# Motor-E.net
KiCad netlist of a schematic drawn in Altium Designer
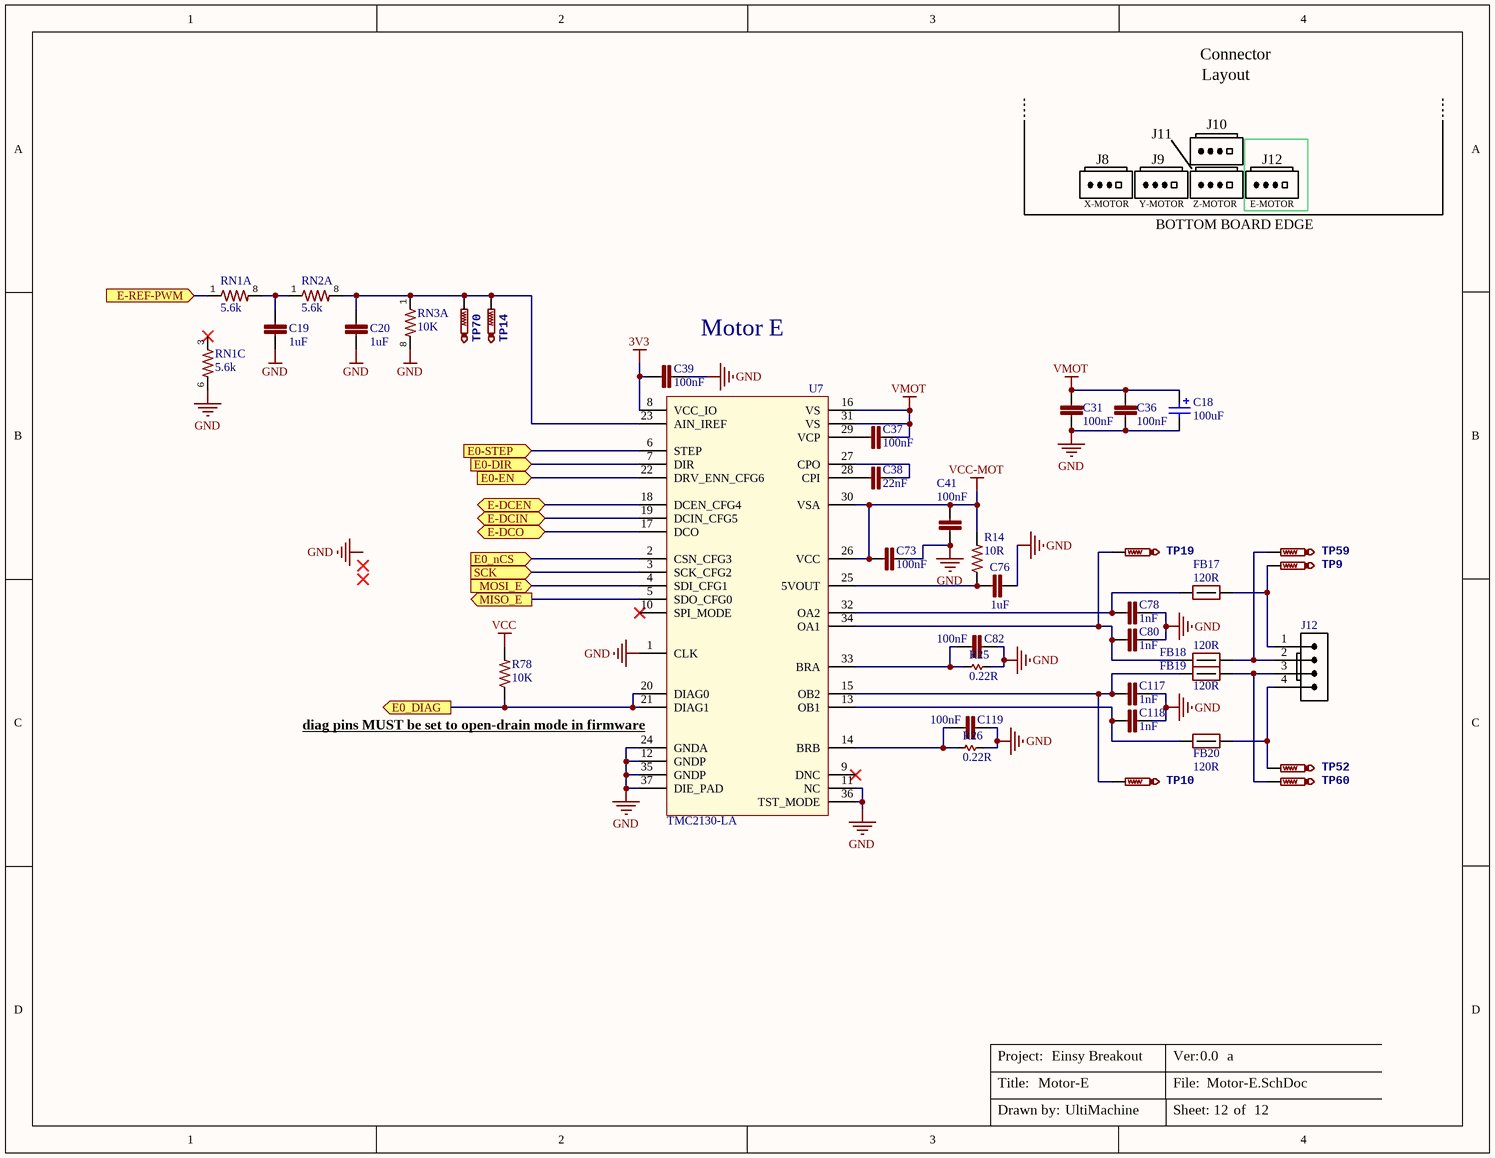
[diagram p0: Motor-E.SchDoc]

(export (version "E")
  (design (tool "Eeschema 10.0.6"))
  (components
    (comp (ref "C18")
      (value "100uF")
      (footprint "CAP-ELEC-063063077")
      (description "CAP ALUM 100UF 35V 20% SMD")
      (fields (field (name "MANUFACTURER") "Nichicon") (field (name "TOLERANCE") "+/- 20%"))
      (libsource (lib "3Delight") (part "UWT1V101MCL1GS"))
    )
    (comp (ref "C19")
      (value "1uF")
      (footprint "C0402")
      (description "CAP CER 0402 1uF 6.3V 10% X5R")
      (fields (field (name "MANUFACTURER") "Murata") (field (name "TOLERANCE") "+/- 10%"))
      (libsource (lib "3Delight") (part "GRM155R60J105KE19D"))
    )
    (comp (ref "C20")
      (value "1uF")
      (footprint "C0402")
      (description "CAP CER 0402 1uF 6.3V 10% X5R")
      (fields (field (name "MANUFACTURER") "Murata") (field (name "TOLERANCE") "+/- 10%"))
      (libsource (lib "3Delight") (part "GRM155R60J105KE19D"))
    )
    (comp (ref "C31")
      (value "100nF")
      (footprint "C0603")
      (description "CAP CER 0603 100nF 50V 10% X7R")
      (fields (field (name "MANUFACTURER") "Kemet") (field (name "TOLERANCE") "+/- 10%"))
      (libsource (lib "") (part "C0603C104K5RACTU_1"))
    )
    (comp (ref "C36")
      (value "100nF")
      (footprint "C0603")
      (description "CAP CER 0603 100nF 50V 10% X7R")
      (fields (field (name "MANUFACTURER") "Kemet") (field (name "TOLERANCE") "+/- 10%"))
      (libsource (lib "") (part "C0603C104K5RACTU_1"))
    )
    (comp (ref "C37")
      (value "100nF")
      (footprint "C0603")
      (description "CAP CER 0603 100nF 50V 10% X7R")
      (fields (field (name "MANUFACTURER") "Kemet") (field (name "TOLERANCE") "+/- 10%"))
      (libsource (lib "") (part "C0603C104K5RACTU_2"))
    )
    (comp (ref "C38")
      (value "22nF")
      (footprint "C0402")
      (description "CAP CER 0402 22nF ±10% 50V X7R")
      (fields (field (name "MANUFACTURER") "YAGEO") (field (name "TOLERANCE") "+/- 10%"))
      (libsource (lib "3Delight") (part "GCM155R71H223KA55D"))
    )
    (comp (ref "C39")
      (value "100nF")
      (footprint "C0402")
      (description "CAP CER 0402 100nF 16V 10% X7R")
      (fields (field (name "MANUFACTURER") "Murata") (field (name "TOLERANCE") "+/- 10%"))
      (libsource (lib "") (part "GRM155R71C104KA88D_1"))
    )
    (comp (ref "C41")
      (value "100nF")
      (footprint "C0402")
      (description "CAP CER 0402 100nF 16V 10% X7R")
      (fields (field (name "MANUFACTURER") "Murata") (field (name "TOLERANCE") "+/- 10%"))
      (libsource (lib "3Delight") (part "GRM155R71C104KA88D"))
    )
    (comp (ref "C73")
      (value "100nF")
      (footprint "C0402")
      (description "CAP CER 0402 100nF 16V 10% X7R")
      (fields (field (name "MANUFACTURER") "Murata") (field (name "TOLERANCE") "+/- 10%"))
      (libsource (lib "") (part "GRM155R71C104KA88D_1"))
    )
    (comp (ref "C76")
      (value "1uF")
      (footprint "C0402")
      (description "CAP CER 0402 1uF 6.3V 10% X5R")
      (fields (field (name "MANUFACTURER") "Murata") (field (name "TOLERANCE") "+/- 10%"))
      (libsource (lib "") (part "GRM155R60J105KE19D_1"))
    )
    (comp (ref "C78")
      (value "1nF")
      (footprint "C0603")
      (description "CAP CER 0603  1nF 50v 10% X7R")
      (fields (field (name "MANUFACTURER") "Kemet") (field (name "TOLERANCE") "+/- 10%"))
      (libsource (lib "3Delight") (part "C0603C102K5RACTU"))
    )
    (comp (ref "C80")
      (value "1nF")
      (footprint "C0603")
      (description "CAP CER 0603  1nF 50v 10% X7R")
      (fields (field (name "MANUFACTURER") "Kemet") (field (name "TOLERANCE") "+/- 10%"))
      (libsource (lib "3Delight") (part "C0603C102K5RACTU"))
    )
    (comp (ref "C82")
      (value "100nF")
      (footprint "C0603")
      (description "CAP CER 0603 100nF 50V 10% X7R")
      (fields (field (name "MANUFACTURER") "Kemet") (field (name "TOLERANCE") "+/- 10%"))
      (libsource (lib "3Delight") (part "C0603C104K5RACTU"))
    )
    (comp (ref "C117")
      (value "1nF")
      (footprint "C0603")
      (description "CAP CER 0603  1nF 50v 10% X7R")
      (fields (field (name "MANUFACTURER") "Kemet") (field (name "TOLERANCE") "+/- 10%"))
      (libsource (lib "3Delight") (part "C0603C102K5RACTU"))
    )
    (comp (ref "C118")
      (value "1nF")
      (footprint "C0603")
      (description "CAP CER 0603  1nF 50v 10% X7R")
      (fields (field (name "MANUFACTURER") "Kemet") (field (name "TOLERANCE") "+/- 10%"))
      (libsource (lib "3Delight") (part "C0603C102K5RACTU"))
    )
    (comp (ref "C119")
      (value "100nF")
      (footprint "C0603")
      (description "CAP CER 0603 100nF 50V 10% X7R")
      (fields (field (name "MANUFACTURER") "Kemet") (field (name "TOLERANCE") "+/- 10%"))
      (libsource (lib "3Delight") (part "C0603C104K5RACTU"))
    )
    (comp (ref "FB17")
      (value "120R")
      (footprint "FB0603")
      (description "FERRITE BEAD 120 OHM 0603 1LN")
      (fields (field (name "MANUFACTURER") "Samsung") (field (name "PART") "FERRITE 120R 3A 0603"))
      (libsource (lib "Inductors") (part "FERRITE 120R 3A 0603"))
    )
    (comp (ref "FB18")
      (value "120R")
      (footprint "FB0603")
      (description "FERRITE BEAD 120 OHM 0603 1LN")
      (fields (field (name "MANUFACTURER") "Samsung") (field (name "PART") "FERRITE 120R 3A 0603"))
      (libsource (lib "Inductors") (part "FERRITE 120R 3A 0603"))
    )
    (comp (ref "FB19")
      (value "120R")
      (footprint "FB0603")
      (description "FERRITE BEAD 120 OHM 0603 1LN")
      (fields (field (name "MANUFACTURER") "Samsung") (field (name "PART") "FERRITE 120R 3A 0603"))
      (libsource (lib "Inductors") (part "FERRITE 120R 3A 0603"))
    )
    (comp (ref "FB20")
      (value "120R")
      (footprint "FB0603")
      (description "FERRITE BEAD 120 OHM 0603 1LN")
      (fields (field (name "MANUFACTURER") "Samsung") (field (name "PART") "FERRITE 120R 3A 0603"))
      (libsource (lib "Inductors") (part "FERRITE 120R 3A 0603"))
    )
    (comp (ref "J12")
      (value "Molex 0705430003")
      (footprint "4POL254")
      (description "Molex 4 Pin Clip Connector")
      (fields (field (name "MANUFACTURER") "Molex") (field (name "PART") "4 Pin Conn"))
      (libsource (lib "3Delight") (part "CONN 4PIN 0.1{dblquote} VERT SHRD LOCK ALT"))
    )
    (comp (ref "R14")
      (value "10R")
      (footprint "R0402")
      (description "RES SMD 10 OHM 1% 1/16W 0402")
      (fields (field (name "MANUFACTURER") "Yageo") (field (name "TOLERANCE") "+/- 1%"))
      (libsource (lib "3Delight") (part "RC0402FR-0710RL"))
    )
    (comp (ref "R25")
      (value "0.22R")
      (footprint "R1206")
      (description "RES SMD 0.22 OHM 1% 1/3W 1206")
      (fields (field (name "MANUFACTURER") "Panasonic") (field (name "TOLERANCE") "+/- 1%"))
      (libsource (lib "Resistors") (part "0.22R 1% 1206"))
    )
    (comp (ref "R26")
      (value "0.22R")
      (footprint "R1206")
      (description "RES SMD 0.22 OHM 1% 1/3W 1206")
      (fields (field (name "MANUFACTURER") "Panasonic") (field (name "TOLERANCE") "+/- 1%"))
      (libsource (lib "Resistors") (part "0.22R 1% 1206"))
    )
    (comp (ref "R78")
      (value "10K")
      (footprint "R0402")
      (description "RES SMD 10K OHM 1% 1/16W 0402")
      (fields (field (name "MANUFACTURER") "Yageo") (field (name "PART") "10k 1% 0402"))
      (libsource (lib "3Delight") (part "RC0402FR-0710KP"))
    )
    (comp (ref "RN1")
      (value "5.6k")
      (footprint "CAY16")
      (description "RES ARRAY 4 RES 5.6K OHM 1206")
      (fields (field (name "MANUFACTURER") "Bourns") (field (name "TOLERANCE") "+/- 5%"))
      (libsource (lib "Resistors") (part "5.6k x 4 5% 1206"))
    )
    (comp (ref "RN2")
      (value "5.6k")
      (footprint "CAY16")
      (description "RES ARRAY 4 RES 5.6K OHM 1206")
      (fields (field (name "MANUFACTURER") "Bourns") (field (name "TOLERANCE") "+/- 5%"))
      (libsource (lib "Resistors") (part "5.6k x 4 5% 1206"))
    )
    (comp (ref "RN3")
      (value "10K")
      (footprint "CAY16")
      (description "RES ARRAY 4 RES 10K 1206 62.5mW 5%")
      (fields (field (name "MANUFACTURER") "Bourns") (field (name "TOLERANCE") "+/- 5%"))
      (libsource (lib "3Delight") (part "CAY16-103J4LF"))
    )
    (comp (ref "TP9")
      (value "TestPoint")
      (footprint "TP1-27")
      (description "Test Point")
      (libsource (lib "3Delight") (part "TestPoint"))
    )
    (comp (ref "TP10")
      (value "TestPoint")
      (footprint "TP1-27")
      (description "Test Point")
      (libsource (lib "3Delight") (part "TestPoint"))
    )
    (comp (ref "TP14")
      (value "TestPoint")
      (footprint "TP1-27")
      (description "Test Point")
      (libsource (lib "") (part "TestPoint_1"))
    )
    (comp (ref "TP19")
      (value "TestPoint")
      (footprint "TP1-27")
      (description "Test Point")
      (libsource (lib "3Delight") (part "TestPoint"))
    )
    (comp (ref "TP52")
      (value "TestPoint")
      (footprint "TP1-27")
      (description "Test Point")
      (libsource (lib "3Delight") (part "TestPoint"))
    )
    (comp (ref "TP59")
      (value "TestPoint")
      (footprint "TP1-27")
      (description "Test Point")
      (libsource (lib "3Delight") (part "TestPoint"))
    )
    (comp (ref "TP60")
      (value "TestPoint")
      (footprint "TP1-27")
      (description "Test Point")
      (libsource (lib "3Delight") (part "TestPoint"))
    )
    (comp (ref "TP70")
      (value "TestPoint")
      (footprint "TP1-27")
      (description "Test Point")
      (libsource (lib "") (part "TestPoint_1"))
    )
    (comp (ref "U7")
      (value "TMC2130-LA")
      (footprint "QFN36-50P500X600X900_HS-37N")
      (description "IC STEPPER MOTOR DVR SPI 36QFN")
      (fields (field (name "MANUFACTURER") "Trinamic") (field (name "PART") "TMC2130"))
      (libsource (lib "ICs-Motor Controller") (part "TMC2130-LA-T"))
    )
  )
  (nets
    (net (code "1") (name "/E-DCEN") (class "Default")
      (node (ref "U7") (pin "18") (pinfunction "DCEN_CFG4_18") (pintype "passive"))
    )
    (net (code "2") (name "/E-DCIN") (class "Default")
      (node (ref "U7") (pin "19") (pinfunction "DCIN_CFG5_19") (pintype "passive"))
    )
    (net (code "3") (name "/E-DCO") (class "Default")
      (node (ref "U7") (pin "17") (pinfunction "DCO_17") (pintype "passive"))
    )
    (net (code "4") (name "/E-REF-PWM") (class "Default")
      (node (ref "RN1") (pin "1") (pinfunction "1_1") (pintype "passive"))
    )
    (net (code "5") (name "/E0-DIR") (class "Default")
      (node (ref "U7") (pin "7") (pinfunction "DIR_7") (pintype "passive"))
    )
    (net (code "6") (name "/E0-EN") (class "Default")
      (node (ref "U7") (pin "22") (pinfunction "DRV_ENN_CFG6_22") (pintype "passive"))
    )
    (net (code "7") (name "/E0-STEP") (class "Default")
      (node (ref "U7") (pin "6") (pinfunction "STEP_6") (pintype "passive"))
    )
    (net (code "8") (name "/E0_DIAG") (class "Default")
      (node (ref "R78") (pin "1") (pinfunction "1_1") (pintype "passive"))
      (node (ref "U7") (pin "20") (pinfunction "DIAG0_20") (pintype "passive"))
      (node (ref "U7") (pin "21") (pinfunction "DIAG1_21") (pintype "passive"))
    )
    (net (code "9") (name "/E0_nCS") (class "Default")
      (node (ref "U7") (pin "2") (pinfunction "CSN_CFG3_2") (pintype "passive"))
    )
    (net (code "10") (name "/MISO_E") (class "Default")
      (node (ref "U7") (pin "5") (pinfunction "SDO_CFG0_5") (pintype "passive"))
    )
    (net (code "11") (name "/MOSI_E") (class "Default")
      (node (ref "U7") (pin "4") (pinfunction "SDI_CFG1_4") (pintype "passive"))
    )
    (net (code "12") (name "/SCK") (class "Default")
      (node (ref "U7") (pin "3") (pinfunction "SCK_CFG2_3") (pintype "passive"))
    )
    (net (code "13") (name "3V3") (class "Default")
      (node (ref "C39") (pin "2") (pinfunction "2_2") (pintype "passive"))
      (node (ref "U7") (pin "8") (pinfunction "VCC_IO_8") (pintype "passive"))
    )
    (net (code "14") (name "GND") (class "Default")
      (node (ref "C117") (pin "2") (pinfunction "2_2") (pintype "passive"))
      (node (ref "C118") (pin "2") (pinfunction "2_2") (pintype "passive"))
      (node (ref "C119") (pin "1") (pinfunction "1_1") (pintype "passive"))
      (node (ref "C18") (pin "2") (pinfunction "2_2") (pintype "passive"))
      (node (ref "C19") (pin "2") (pinfunction "2_2") (pintype "passive"))
      (node (ref "C20") (pin "2") (pinfunction "2_2") (pintype "passive"))
      (node (ref "C31") (pin "1") (pinfunction "1_1") (pintype "passive"))
      (node (ref "C36") (pin "1") (pinfunction "1_1") (pintype "passive"))
      (node (ref "C39") (pin "1") (pinfunction "1_1") (pintype "passive"))
      (node (ref "C41") (pin "1") (pinfunction "1_1") (pintype "passive"))
      (node (ref "C73") (pin "1") (pinfunction "1_1") (pintype "passive"))
      (node (ref "C76") (pin "2") (pinfunction "2_2") (pintype "passive"))
      (node (ref "C78") (pin "2") (pinfunction "2_2") (pintype "passive"))
      (node (ref "C80") (pin "2") (pinfunction "2_2") (pintype "passive"))
      (node (ref "C82") (pin "1") (pinfunction "1_1") (pintype "passive"))
      (node (ref "R25") (pin "2") (pinfunction "2_2") (pintype "passive"))
      (node (ref "R26") (pin "2") (pinfunction "2_2") (pintype "passive"))
      (node (ref "RN1") (pin "6") (pinfunction "2_6") (pintype "passive"))
      (node (ref "RN3") (pin "8") (pinfunction "2_8") (pintype "passive"))
      (node (ref "U7") (pin "1") (pinfunction "CLK_1") (pintype "passive"))
      (node (ref "U7") (pin "11") (pinfunction "NC_11") (pintype "passive"))
      (node (ref "U7") (pin "12") (pinfunction "GNDP_12") (pintype "passive"))
      (node (ref "U7") (pin "24") (pinfunction "GNDA_24") (pintype "passive"))
      (node (ref "U7") (pin "35") (pinfunction "GNDP_35") (pintype "passive"))
      (node (ref "U7") (pin "36") (pinfunction "TST_MODE_36") (pintype "passive"))
      (node (ref "U7") (pin "37") (pinfunction "DIE_PAD_37") (pintype "passive"))
    )
    (net (code "15") (name "Net-(FB17-Pad2)") (class "Default")
      (node (ref "FB17") (pin "2") (pinfunction "2_2") (pintype "passive"))
      (node (ref "J12") (pin "1") (pinfunction "1_1") (pintype "passive"))
      (node (ref "TP9") (pin "TP") (pinfunction "TP_TP") (pintype "passive"))
    )
    (net (code "16") (name "Net-(FB18-Pad2)") (class "Default")
      (node (ref "FB18") (pin "2") (pinfunction "2_2") (pintype "passive"))
      (node (ref "J12") (pin "2") (pinfunction "2_2") (pintype "passive"))
      (node (ref "TP59") (pin "TP") (pinfunction "TP_TP") (pintype "passive"))
    )
    (net (code "17") (name "Net-(FB19-Pad2)") (class "Default")
      (node (ref "FB19") (pin "2") (pinfunction "2_2") (pintype "passive"))
      (node (ref "J12") (pin "3") (pinfunction "3_3") (pintype "passive"))
      (node (ref "TP60") (pin "TP") (pinfunction "TP_TP") (pintype "passive"))
    )
    (net (code "18") (name "Net-(FB20-Pad2)") (class "Default")
      (node (ref "FB20") (pin "2") (pinfunction "2_2") (pintype "passive"))
      (node (ref "J12") (pin "4") (pinfunction "4_4") (pintype "passive"))
      (node (ref "TP52") (pin "TP") (pinfunction "TP_TP") (pintype "passive"))
    )
    (net (code "19") (name "Net-(RN1A-2)") (class "Default")
      (node (ref "C19") (pin "1") (pinfunction "1_1") (pintype "passive"))
      (node (ref "RN1") (pin "8") (pinfunction "2_8") (pintype "passive"))
      (node (ref "RN2") (pin "1") (pinfunction "1_1") (pintype "passive"))
    )
    (net (code "20") (name "Net-(RN2A-2)") (class "Default")
      (node (ref "C20") (pin "1") (pinfunction "1_1") (pintype "passive"))
      (node (ref "RN2") (pin "8") (pinfunction "2_8") (pintype "passive"))
      (node (ref "RN3") (pin "1") (pinfunction "1_1") (pintype "passive"))
      (node (ref "TP14") (pin "TP") (pinfunction "TP_TP") (pintype "passive"))
      (node (ref "TP70") (pin "TP") (pinfunction "TP_TP") (pintype "passive"))
      (node (ref "U7") (pin "23") (pinfunction "AIN_IREF_23") (pintype "passive"))
    )
    (net (code "21") (name "Net-(U7-5VOUT)") (class "Default")
      (node (ref "C76") (pin "1") (pinfunction "1_1") (pintype "passive"))
      (node (ref "R14") (pin "1") (pinfunction "1_1") (pintype "passive"))
      (node (ref "U7") (pin "25") (pinfunction "5VOUT_25") (pintype "passive"))
    )
    (net (code "22") (name "Net-(U7-BRA)") (class "Default")
      (node (ref "C82") (pin "2") (pinfunction "2_2") (pintype "passive"))
      (node (ref "R25") (pin "1") (pinfunction "1_1") (pintype "passive"))
      (node (ref "U7") (pin "33") (pinfunction "BRA_33") (pintype "passive"))
    )
    (net (code "23") (name "Net-(U7-BRB)") (class "Default")
      (node (ref "C119") (pin "2") (pinfunction "2_2") (pintype "passive"))
      (node (ref "R26") (pin "1") (pinfunction "1_1") (pintype "passive"))
      (node (ref "U7") (pin "14") (pinfunction "BRB_14") (pintype "passive"))
    )
    (net (code "24") (name "Net-(U7-CPI)") (class "Default")
      (node (ref "C38") (pin "1") (pinfunction "1_1") (pintype "passive"))
      (node (ref "U7") (pin "28") (pinfunction "CPI_28") (pintype "passive"))
    )
    (net (code "25") (name "Net-(U7-CPO)") (class "Default")
      (node (ref "C38") (pin "2") (pinfunction "2_2") (pintype "passive"))
      (node (ref "U7") (pin "27") (pinfunction "CPO_27") (pintype "passive"))
    )
    (net (code "26") (name "Net-(U7-OA1)") (class "Default")
      (node (ref "C80") (pin "1") (pinfunction "1_1") (pintype "passive"))
      (node (ref "FB18") (pin "1") (pinfunction "1_1") (pintype "passive"))
      (node (ref "TP19") (pin "TP") (pinfunction "TP_TP") (pintype "passive"))
      (node (ref "U7") (pin "34") (pinfunction "OA1_34") (pintype "passive"))
    )
    (net (code "27") (name "Net-(U7-OA2)") (class "Default")
      (node (ref "C78") (pin "1") (pinfunction "1_1") (pintype "passive"))
      (node (ref "FB17") (pin "1") (pinfunction "1_1") (pintype "passive"))
      (node (ref "U7") (pin "32") (pinfunction "OA2_32") (pintype "passive"))
    )
    (net (code "28") (name "Net-(U7-OB1)") (class "Default")
      (node (ref "C118") (pin "1") (pinfunction "1_1") (pintype "passive"))
      (node (ref "FB20") (pin "1") (pinfunction "1_1") (pintype "passive"))
      (node (ref "U7") (pin "13") (pinfunction "OB1_13") (pintype "passive"))
    )
    (net (code "29") (name "Net-(U7-OB2)") (class "Default")
      (node (ref "C117") (pin "1") (pinfunction "1_1") (pintype "passive"))
      (node (ref "FB19") (pin "1") (pinfunction "1_1") (pintype "passive"))
      (node (ref "TP10") (pin "TP") (pinfunction "TP_TP") (pintype "passive"))
      (node (ref "U7") (pin "15") (pinfunction "OB2_15") (pintype "passive"))
    )
    (net (code "30") (name "Net-(U7-VCP)") (class "Default")
      (node (ref "C37") (pin "1") (pinfunction "1_1") (pintype "passive"))
      (node (ref "U7") (pin "29") (pinfunction "VCP_29") (pintype "passive"))
    )
    (net (code "31") (name "VCC") (class "Default")
      (node (ref "R78") (pin "2") (pinfunction "2_2") (pintype "passive"))
    )
    (net (code "32") (name "VCC-MOT") (class "Default")
      (node (ref "C41") (pin "2") (pinfunction "2_2") (pintype "passive"))
      (node (ref "C73") (pin "2") (pinfunction "2_2") (pintype "passive"))
      (node (ref "R14") (pin "2") (pinfunction "2_2") (pintype "passive"))
      (node (ref "U7") (pin "26") (pinfunction "VCC_26") (pintype "passive"))
      (node (ref "U7") (pin "30") (pinfunction "VSA_30") (pintype "passive"))
    )
    (net (code "33") (name "VMOT") (class "Default")
      (node (ref "C18") (pin "1") (pinfunction "1_1") (pintype "passive"))
      (node (ref "C31") (pin "2") (pinfunction "2_2") (pintype "passive"))
      (node (ref "C36") (pin "2") (pinfunction "2_2") (pintype "passive"))
      (node (ref "C37") (pin "2") (pinfunction "2_2") (pintype "passive"))
      (node (ref "U7") (pin "16") (pinfunction "VS_16") (pintype "passive"))
      (node (ref "U7") (pin "31") (pinfunction "VS_31") (pintype "passive"))
    )
    (net (code "34") (name "unconnected-(RN1C-1-Pad3)") (class "Default")
      (node (ref "RN1") (pin "3") (pinfunction "1_3") (pintype "passive+no_connect"))
    )
    (net (code "35") (name "unconnected-(U7-DNC-Pad9)") (class "Default")
      (node (ref "U7") (pin "9") (pinfunction "DNC_9") (pintype "passive+no_connect"))
    )
    (net (code "36") (name "unconnected-(U7-SPI_MODE-Pad10)") (class "Default")
      (node (ref "U7") (pin "10") (pinfunction "SPI_MODE_10") (pintype "passive+no_connect"))
    )
  )
)
